# Adafruit_PCA9685_rev_C.net
KiCad netlist of a schematic drawn in EAGLE
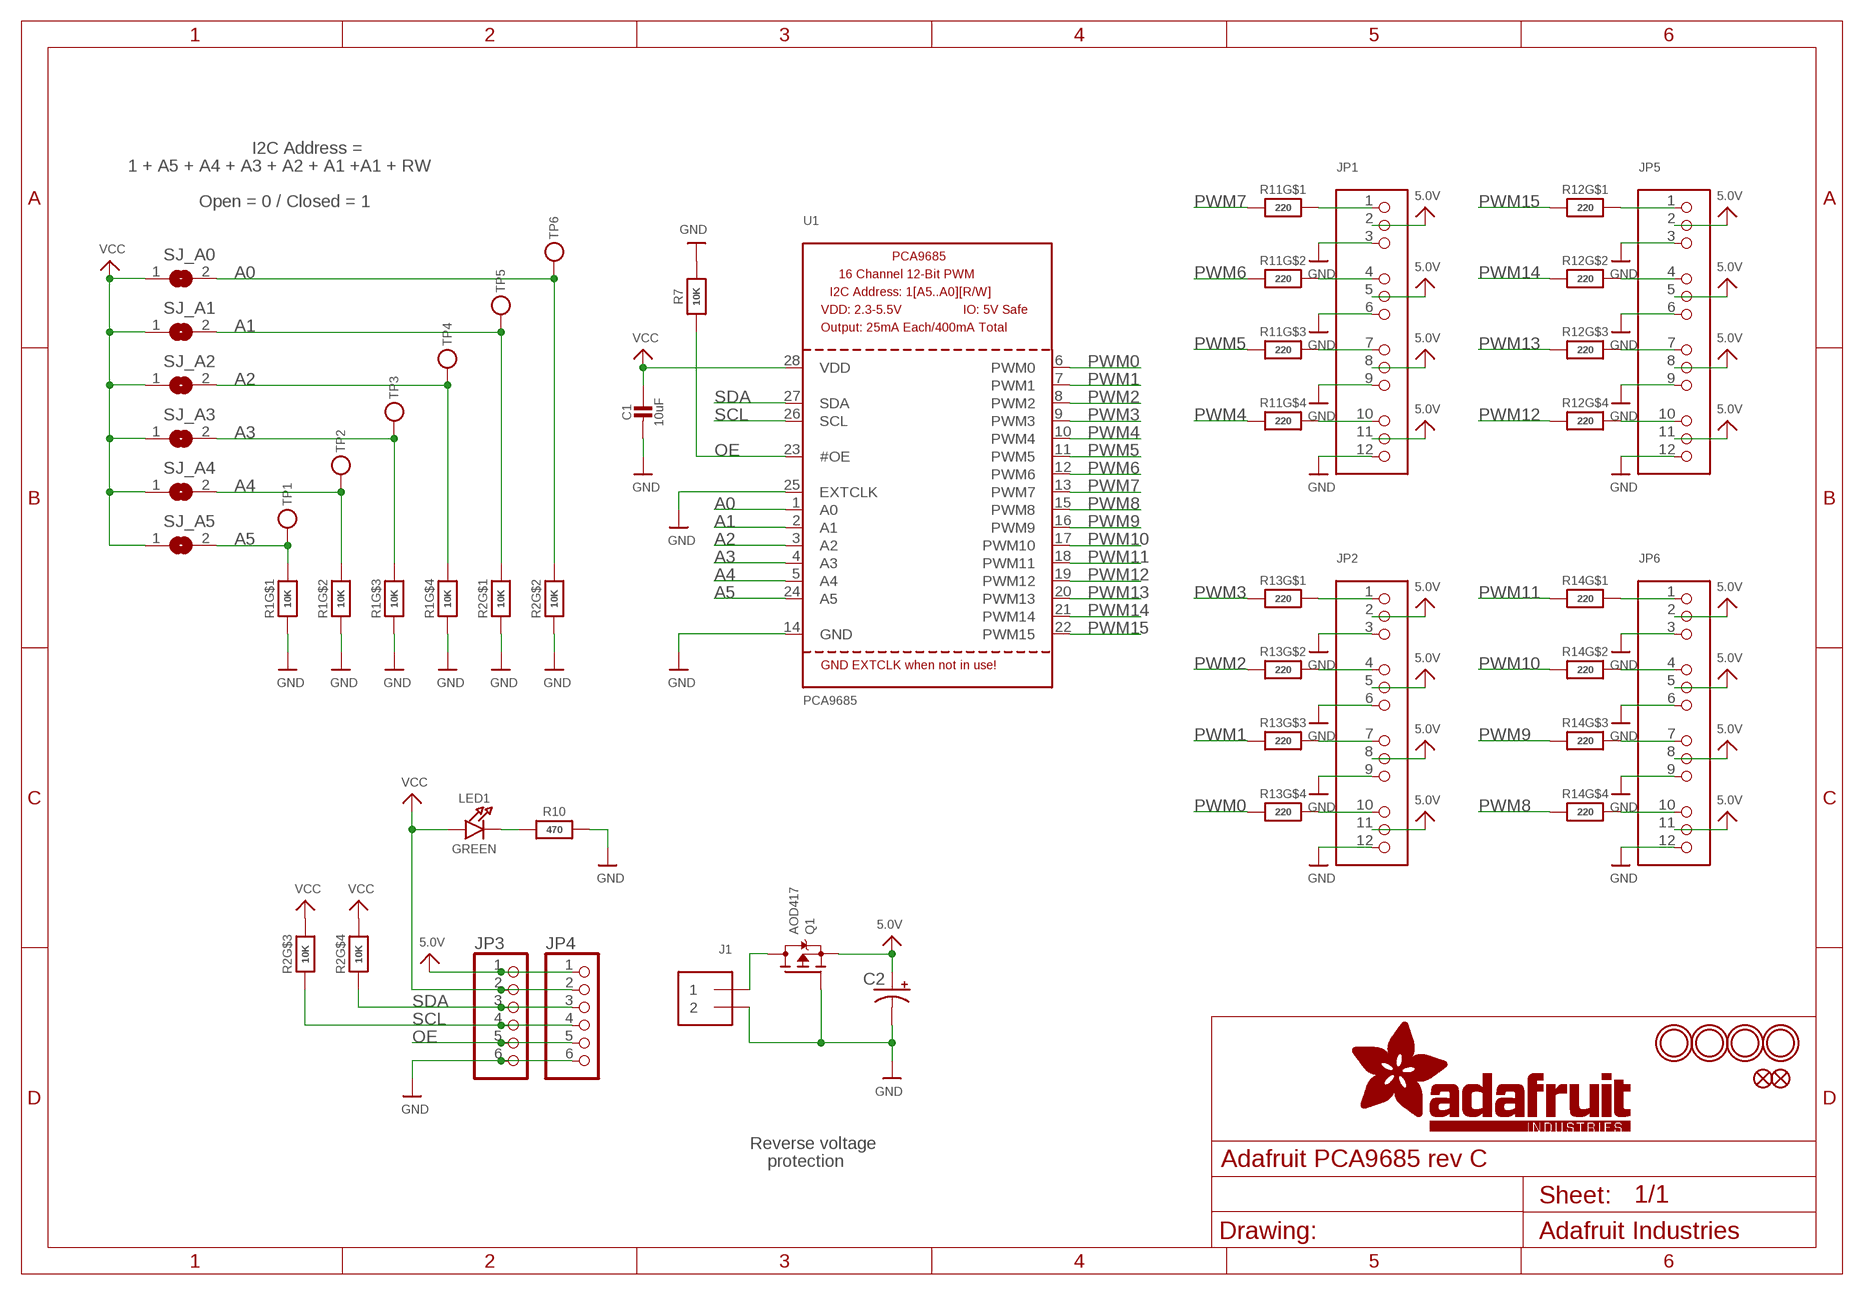
[diagram p0: schematic, sheet 1]

(export (version "E")
  (design (tool "Eeschema 10.0.6"))
  (components
    (comp (ref "C1")
      (value "10uF")
      (footprint "eagle-import:0805-NO")
      (libsource (lib "eagle-import") (part "CAP_CERAMIC0805-NOOUTLINE"))
    )
    (comp (ref "C2")
      (value "CPOL-USE3.5-8")
      (footprint "eagle-import:E3,5-8")
      (libsource (lib "eagle-import") (part "CPOL-USE3.5-8"))
    )
    (comp (ref "FID1")
      (value "FIDUCIAL\"\"")
      (footprint "eagle-import:FIDUCIAL_1MM")
      (libsource (lib "eagle-import") (part "FIDUCIAL{dblquote}{dblquote}"))
    )
    (comp (ref "FID2")
      (value "FIDUCIAL\"\"")
      (footprint "eagle-import:FIDUCIAL_1MM")
      (libsource (lib "eagle-import") (part "FIDUCIAL{dblquote}{dblquote}"))
    )
    (comp (ref "J1")
      (value "TERMBLOCK_1X2")
      (footprint "eagle-import:TERMBLOCK_1X2-3.5MM")
      (libsource (lib "eagle-import") (part "TERMBLOCK_1X2"))
    )
    (comp (ref "JP1")
      (value "HEADER-3X04")
      (footprint "eagle-import:3X04")
      (libsource (lib "eagle-import") (part "HEADER-3X04"))
    )
    (comp (ref "JP2")
      (value "HEADER-3X04")
      (footprint "eagle-import:3X04")
      (libsource (lib "eagle-import") (part "HEADER-3X04"))
    )
    (comp (ref "JP3")
      (value "PINHD-1X6CB")
      (footprint "eagle-import:1X06-CLEANBIG")
      (libsource (lib "eagle-import") (part "PINHD-1X6CB"))
    )
    (comp (ref "JP4")
      (value "PINHD-1X6CB")
      (footprint "eagle-import:1X06-CLEANBIG")
      (libsource (lib "eagle-import") (part "PINHD-1X6CB"))
    )
    (comp (ref "JP5")
      (value "HEADER-3X04")
      (footprint "eagle-import:3X04")
      (libsource (lib "eagle-import") (part "HEADER-3X04"))
    )
    (comp (ref "JP6")
      (value "HEADER-3X04")
      (footprint "eagle-import:3X04")
      (libsource (lib "eagle-import") (part "HEADER-3X04"))
    )
    (comp (ref "LED1")
      (value "GREEN")
      (footprint "eagle-import:CHIPLED_0805_NOOUTLINE")
      (libsource (lib "eagle-import") (part "LED0805_NOOUTLINE"))
    )
    (comp (ref "Q1")
      (value "AOD417")
      (footprint "eagle-import:TO252")
      (libsource (lib "eagle-import") (part "MOSFET-PTO252"))
    )
    (comp (ref "R1")
      (value "10K")
      (footprint "eagle-import:RESPACK_4X0603")
      (libsource (lib "eagle-import") (part "RESISTOR_4PACK"))
    )
    (comp (ref "R2")
      (value "10K")
      (footprint "eagle-import:RESPACK_4X0603")
      (libsource (lib "eagle-import") (part "RESISTOR_4PACK"))
    )
    (comp (ref "R7")
      (value "10K")
      (footprint "eagle-import:0805-NO")
      (libsource (lib "eagle-import") (part "RESISTOR0805_NOOUTLINE"))
    )
    (comp (ref "R10")
      (value "470")
      (footprint "eagle-import:_0805MP")
      (libsource (lib "eagle-import") (part "RESISTOR_0805MP"))
    )
    (comp (ref "R11")
      (value "220")
      (footprint "eagle-import:RESPACK_4X0603")
      (libsource (lib "eagle-import") (part "RESISTOR_4PACK"))
    )
    (comp (ref "R12")
      (value "220")
      (footprint "eagle-import:RESPACK_4X0603")
      (libsource (lib "eagle-import") (part "RESISTOR_4PACK"))
    )
    (comp (ref "R13")
      (value "220")
      (footprint "eagle-import:RESPACK_4X0603")
      (libsource (lib "eagle-import") (part "RESISTOR_4PACK"))
    )
    (comp (ref "R14")
      (value "220")
      (footprint "eagle-import:RESPACK_4X0603")
      (libsource (lib "eagle-import") (part "RESISTOR_4PACK"))
    )
    (comp (ref "SJ_A0")
      (value "SOLDERJUMPERREFLOW_NOPASTE")
      (footprint "eagle-import:SOLDERJUMPER_REFLOW_NOPASTE")
      (libsource (lib "eagle-import") (part "SOLDERJUMPERREFLOW_NOPASTE"))
    )
    (comp (ref "SJ_A1")
      (value "SOLDERJUMPERREFLOW_NOPASTE")
      (footprint "eagle-import:SOLDERJUMPER_REFLOW_NOPASTE")
      (libsource (lib "eagle-import") (part "SOLDERJUMPERREFLOW_NOPASTE"))
    )
    (comp (ref "SJ_A2")
      (value "SOLDERJUMPERREFLOW_NOPASTE")
      (footprint "eagle-import:SOLDERJUMPER_REFLOW_NOPASTE")
      (libsource (lib "eagle-import") (part "SOLDERJUMPERREFLOW_NOPASTE"))
    )
    (comp (ref "SJ_A3")
      (value "SOLDERJUMPERREFLOW_NOPASTE")
      (footprint "eagle-import:SOLDERJUMPER_REFLOW_NOPASTE")
      (libsource (lib "eagle-import") (part "SOLDERJUMPERREFLOW_NOPASTE"))
    )
    (comp (ref "SJ_A4")
      (value "SOLDERJUMPERREFLOW_NOPASTE")
      (footprint "eagle-import:SOLDERJUMPER_REFLOW_NOPASTE")
      (libsource (lib "eagle-import") (part "SOLDERJUMPERREFLOW_NOPASTE"))
    )
    (comp (ref "SJ_A5")
      (value "SOLDERJUMPERREFLOW_NOPASTE")
      (footprint "eagle-import:SOLDERJUMPER_REFLOW_NOPASTE")
      (libsource (lib "eagle-import") (part "SOLDERJUMPERREFLOW_NOPASTE"))
    )
    (comp (ref "TP1")
      (value "TESTPOINTROUND1MM")
      (footprint "eagle-import:TESTPOINT_ROUND_1MM")
      (libsource (lib "eagle-import") (part "TESTPOINTROUND1MM"))
    )
    (comp (ref "TP2")
      (value "TESTPOINTROUND1MM")
      (footprint "eagle-import:TESTPOINT_ROUND_1MM")
      (libsource (lib "eagle-import") (part "TESTPOINTROUND1MM"))
    )
    (comp (ref "TP3")
      (value "TESTPOINTROUND1MM")
      (footprint "eagle-import:TESTPOINT_ROUND_1MM")
      (libsource (lib "eagle-import") (part "TESTPOINTROUND1MM"))
    )
    (comp (ref "TP4")
      (value "TESTPOINTROUND1MM")
      (footprint "eagle-import:TESTPOINT_ROUND_1MM")
      (libsource (lib "eagle-import") (part "TESTPOINTROUND1MM"))
    )
    (comp (ref "TP5")
      (value "TESTPOINTROUND1MM")
      (footprint "eagle-import:TESTPOINT_ROUND_1MM")
      (libsource (lib "eagle-import") (part "TESTPOINTROUND1MM"))
    )
    (comp (ref "TP6")
      (value "TESTPOINTROUND1MM")
      (footprint "eagle-import:TESTPOINT_ROUND_1MM")
      (libsource (lib "eagle-import") (part "TESTPOINTROUND1MM"))
    )
    (comp (ref "U$47")
      (value "MOUNTINGHOLE2.5")
      (footprint "eagle-import:MOUNTINGHOLE_2.5_PLATED")
      (libsource (lib "eagle-import") (part "MOUNTINGHOLE2.5"))
    )
    (comp (ref "U$48")
      (value "MOUNTINGHOLE2.5")
      (footprint "eagle-import:MOUNTINGHOLE_2.5_PLATED")
      (libsource (lib "eagle-import") (part "MOUNTINGHOLE2.5"))
    )
    (comp (ref "U$49")
      (value "MOUNTINGHOLE2.5")
      (footprint "eagle-import:MOUNTINGHOLE_2.5_PLATED")
      (libsource (lib "eagle-import") (part "MOUNTINGHOLE2.5"))
    )
    (comp (ref "U$50")
      (value "MOUNTINGHOLE2.5")
      (footprint "eagle-import:MOUNTINGHOLE_2.5_PLATED")
      (libsource (lib "eagle-import") (part "MOUNTINGHOLE2.5"))
    )
    (comp (ref "U1")
      (value "PCA9685")
      (footprint "eagle-import:TSSOP28")
      (libsource (lib "eagle-import") (part "PCA9685"))
    )
  )
  (nets
    (net (code "1") (name "/A0") (class "Default")
      (node (ref "R2") (pin "7") (pinfunction "2_7") (pintype "passive"))
      (node (ref "SJ_A0") (pin "2") (pinfunction "2_2") (pintype "passive"))
      (node (ref "TP6") (pin "P$1") (pinfunction "P$1_P$1") (pintype "bidirectional"))
      (node (ref "U1") (pin "1") (pinfunction "A0_1") (pintype "bidirectional"))
    )
    (net (code "2") (name "/A1") (class "Default")
      (node (ref "R2") (pin "8") (pinfunction "2_8") (pintype "passive"))
      (node (ref "SJ_A1") (pin "2") (pinfunction "2_2") (pintype "passive"))
      (node (ref "TP5") (pin "P$1") (pinfunction "P$1_P$1") (pintype "bidirectional"))
      (node (ref "U1") (pin "2") (pinfunction "A1_2") (pintype "bidirectional"))
    )
    (net (code "3") (name "/A2") (class "Default")
      (node (ref "R1") (pin "5") (pinfunction "2_5") (pintype "passive"))
      (node (ref "SJ_A2") (pin "2") (pinfunction "2_2") (pintype "passive"))
      (node (ref "TP4") (pin "P$1") (pinfunction "P$1_P$1") (pintype "bidirectional"))
      (node (ref "U1") (pin "3") (pinfunction "A2_3") (pintype "bidirectional"))
    )
    (net (code "4") (name "/A3") (class "Default")
      (node (ref "R1") (pin "6") (pinfunction "2_6") (pintype "passive"))
      (node (ref "SJ_A3") (pin "2") (pinfunction "2_2") (pintype "passive"))
      (node (ref "TP3") (pin "P$1") (pinfunction "P$1_P$1") (pintype "bidirectional"))
      (node (ref "U1") (pin "4") (pinfunction "A3_4") (pintype "bidirectional"))
    )
    (net (code "5") (name "/A4") (class "Default")
      (node (ref "R1") (pin "7") (pinfunction "2_7") (pintype "passive"))
      (node (ref "SJ_A4") (pin "2") (pinfunction "2_2") (pintype "passive"))
      (node (ref "TP2") (pin "P$1") (pinfunction "P$1_P$1") (pintype "bidirectional"))
      (node (ref "U1") (pin "5") (pinfunction "A4_5") (pintype "bidirectional"))
    )
    (net (code "6") (name "/A5") (class "Default")
      (node (ref "R1") (pin "8") (pinfunction "2_8") (pintype "passive"))
      (node (ref "SJ_A5") (pin "2") (pinfunction "2_2") (pintype "passive"))
      (node (ref "TP1") (pin "P$1") (pinfunction "P$1_P$1") (pintype "bidirectional"))
      (node (ref "U1") (pin "24") (pinfunction "A5_24") (pintype "bidirectional"))
    )
    (net (code "7") (name "/OE") (class "Default")
      (node (ref "JP3") (pin "5") (pinfunction "5_5") (pintype "passive"))
      (node (ref "JP4") (pin "5") (pinfunction "5_5") (pintype "passive"))
      (node (ref "R7") (pin "1") (pinfunction "1_1") (pintype "passive"))
      (node (ref "U1") (pin "23") (pinfunction "#OE_23") (pintype "input"))
    )
    (net (code "8") (name "/PWM0") (class "Default")
      (node (ref "R13") (pin "4") (pinfunction "1_4") (pintype "passive"))
      (node (ref "U1") (pin "6") (pinfunction "PWM0_6") (pintype "output"))
    )
    (net (code "9") (name "/PWM1") (class "Default")
      (node (ref "R13") (pin "3") (pinfunction "1_3") (pintype "passive"))
      (node (ref "U1") (pin "7") (pinfunction "PWM1_7") (pintype "output"))
    )
    (net (code "10") (name "/PWM2") (class "Default")
      (node (ref "R13") (pin "2") (pinfunction "1_2") (pintype "passive"))
      (node (ref "U1") (pin "8") (pinfunction "PWM2_8") (pintype "output"))
    )
    (net (code "11") (name "/PWM3") (class "Default")
      (node (ref "R13") (pin "1") (pinfunction "1_1") (pintype "passive"))
      (node (ref "U1") (pin "9") (pinfunction "PWM3_9") (pintype "output"))
    )
    (net (code "12") (name "/PWM4") (class "Default")
      (node (ref "R11") (pin "4") (pinfunction "1_4") (pintype "passive"))
      (node (ref "U1") (pin "10") (pinfunction "PWM4_10") (pintype "output"))
    )
    (net (code "13") (name "/PWM5") (class "Default")
      (node (ref "R11") (pin "3") (pinfunction "1_3") (pintype "passive"))
      (node (ref "U1") (pin "11") (pinfunction "PWM5_11") (pintype "output"))
    )
    (net (code "14") (name "/PWM6") (class "Default")
      (node (ref "R11") (pin "2") (pinfunction "1_2") (pintype "passive"))
      (node (ref "U1") (pin "12") (pinfunction "PWM6_12") (pintype "output"))
    )
    (net (code "15") (name "/PWM7") (class "Default")
      (node (ref "R11") (pin "1") (pinfunction "1_1") (pintype "passive"))
      (node (ref "U1") (pin "13") (pinfunction "PWM7_13") (pintype "output"))
    )
    (net (code "16") (name "/PWM8") (class "Default")
      (node (ref "R14") (pin "4") (pinfunction "1_4") (pintype "passive"))
      (node (ref "U1") (pin "15") (pinfunction "PWM8_15") (pintype "output"))
    )
    (net (code "17") (name "/PWM9") (class "Default")
      (node (ref "R14") (pin "3") (pinfunction "1_3") (pintype "passive"))
      (node (ref "U1") (pin "16") (pinfunction "PWM9_16") (pintype "output"))
    )
    (net (code "18") (name "/PWM10") (class "Default")
      (node (ref "R14") (pin "2") (pinfunction "1_2") (pintype "passive"))
      (node (ref "U1") (pin "17") (pinfunction "PWM10_17") (pintype "output"))
    )
    (net (code "19") (name "/PWM11") (class "Default")
      (node (ref "R14") (pin "1") (pinfunction "1_1") (pintype "passive"))
      (node (ref "U1") (pin "18") (pinfunction "PWM11_18") (pintype "output"))
    )
    (net (code "20") (name "/PWM12") (class "Default")
      (node (ref "R12") (pin "4") (pinfunction "1_4") (pintype "passive"))
      (node (ref "U1") (pin "19") (pinfunction "PWM12_19") (pintype "output"))
    )
    (net (code "21") (name "/PWM13") (class "Default")
      (node (ref "R12") (pin "3") (pinfunction "1_3") (pintype "passive"))
      (node (ref "U1") (pin "20") (pinfunction "PWM13_20") (pintype "output"))
    )
    (net (code "22") (name "/PWM14") (class "Default")
      (node (ref "R12") (pin "2") (pinfunction "1_2") (pintype "passive"))
      (node (ref "U1") (pin "21") (pinfunction "PWM14_21") (pintype "output"))
    )
    (net (code "23") (name "/PWM15") (class "Default")
      (node (ref "R12") (pin "1") (pinfunction "1_1") (pintype "passive"))
      (node (ref "U1") (pin "22") (pinfunction "PWM15_22") (pintype "output"))
    )
    (net (code "24") (name "/SCL") (class "Default")
      (node (ref "JP3") (pin "4") (pinfunction "4_4") (pintype "passive"))
      (node (ref "JP4") (pin "4") (pinfunction "4_4") (pintype "passive"))
      (node (ref "R2") (pin "3") (pinfunction "1_3") (pintype "passive"))
      (node (ref "U1") (pin "26") (pinfunction "SCL_26") (pintype "bidirectional"))
    )
    (net (code "25") (name "/SDA") (class "Default")
      (node (ref "JP3") (pin "3") (pinfunction "3_3") (pintype "passive"))
      (node (ref "JP4") (pin "3") (pinfunction "3_3") (pintype "passive"))
      (node (ref "R2") (pin "4") (pinfunction "1_4") (pintype "passive"))
      (node (ref "U1") (pin "27") (pinfunction "SDA_27") (pintype "bidirectional"))
    )
    (net (code "26") (name "5.0V") (class "Default")
      (node (ref "C2") (pin "+") (pinfunction "+_+") (pintype "passive"))
      (node (ref "JP1") (pin "11") (pinfunction "11_11") (pintype "passive"))
      (node (ref "JP1") (pin "2") (pinfunction "2_2") (pintype "passive"))
      (node (ref "JP1") (pin "5") (pinfunction "5_5") (pintype "passive"))
      (node (ref "JP1") (pin "8") (pinfunction "8_8") (pintype "passive"))
      (node (ref "JP2") (pin "11") (pinfunction "11_11") (pintype "passive"))
      (node (ref "JP2") (pin "2") (pinfunction "2_2") (pintype "passive"))
      (node (ref "JP2") (pin "5") (pinfunction "5_5") (pintype "passive"))
      (node (ref "JP2") (pin "8") (pinfunction "8_8") (pintype "passive"))
      (node (ref "JP3") (pin "1") (pinfunction "1_1") (pintype "passive"))
      (node (ref "JP4") (pin "1") (pinfunction "1_1") (pintype "passive"))
      (node (ref "JP5") (pin "11") (pinfunction "11_11") (pintype "passive"))
      (node (ref "JP5") (pin "2") (pinfunction "2_2") (pintype "passive"))
      (node (ref "JP5") (pin "5") (pinfunction "5_5") (pintype "passive"))
      (node (ref "JP5") (pin "8") (pinfunction "8_8") (pintype "passive"))
      (node (ref "JP6") (pin "11") (pinfunction "11_11") (pintype "passive"))
      (node (ref "JP6") (pin "2") (pinfunction "2_2") (pintype "passive"))
      (node (ref "JP6") (pin "5") (pinfunction "5_5") (pintype "passive"))
      (node (ref "JP6") (pin "8") (pinfunction "8_8") (pintype "passive"))
      (node (ref "Q1") (pin "2") (pinfunction "S_2") (pintype "passive"))
    )
    (net (code "27") (name "GND") (class "Default")
      (node (ref "C1") (pin "2") (pinfunction "2_2") (pintype "passive"))
      (node (ref "C2") (pin "-") (pinfunction "-_-") (pintype "passive"))
      (node (ref "J1") (pin "2") (pinfunction "2_2") (pintype "passive"))
      (node (ref "JP1") (pin "12") (pinfunction "12_12") (pintype "passive"))
      (node (ref "JP1") (pin "3") (pinfunction "3_3") (pintype "passive"))
      (node (ref "JP1") (pin "6") (pinfunction "6_6") (pintype "passive"))
      (node (ref "JP1") (pin "9") (pinfunction "9_9") (pintype "passive"))
      (node (ref "JP2") (pin "12") (pinfunction "12_12") (pintype "passive"))
      (node (ref "JP2") (pin "3") (pinfunction "3_3") (pintype "passive"))
      (node (ref "JP2") (pin "6") (pinfunction "6_6") (pintype "passive"))
      (node (ref "JP2") (pin "9") (pinfunction "9_9") (pintype "passive"))
      (node (ref "JP3") (pin "6") (pinfunction "6_6") (pintype "passive"))
      (node (ref "JP4") (pin "6") (pinfunction "6_6") (pintype "passive"))
      (node (ref "JP5") (pin "12") (pinfunction "12_12") (pintype "passive"))
      (node (ref "JP5") (pin "3") (pinfunction "3_3") (pintype "passive"))
      (node (ref "JP5") (pin "6") (pinfunction "6_6") (pintype "passive"))
      (node (ref "JP5") (pin "9") (pinfunction "9_9") (pintype "passive"))
      (node (ref "JP6") (pin "12") (pinfunction "12_12") (pintype "passive"))
      (node (ref "JP6") (pin "3") (pinfunction "3_3") (pintype "passive"))
      (node (ref "JP6") (pin "6") (pinfunction "6_6") (pintype "passive"))
      (node (ref "JP6") (pin "9") (pinfunction "9_9") (pintype "passive"))
      (node (ref "Q1") (pin "1") (pinfunction "G_1") (pintype "passive"))
      (node (ref "R1") (pin "1") (pinfunction "1_1") (pintype "passive"))
      (node (ref "R1") (pin "2") (pinfunction "1_2") (pintype "passive"))
      (node (ref "R1") (pin "3") (pinfunction "1_3") (pintype "passive"))
      (node (ref "R1") (pin "4") (pinfunction "1_4") (pintype "passive"))
      (node (ref "R10") (pin "2") (pinfunction "2_2") (pintype "passive"))
      (node (ref "R2") (pin "1") (pinfunction "1_1") (pintype "passive"))
      (node (ref "R2") (pin "2") (pinfunction "1_2") (pintype "passive"))
      (node (ref "R7") (pin "2") (pinfunction "2_2") (pintype "passive"))
      (node (ref "U1") (pin "14") (pinfunction "GND_14") (pintype "power_in"))
      (node (ref "U1") (pin "25") (pinfunction "EXTCLK_25") (pintype "input"))
    )
    (net (code "28") (name "Net-(LED1-PadC)") (class "Default")
      (node (ref "LED1") (pin "C") (pinfunction "C_C") (pintype "passive"))
      (node (ref "R10") (pin "1") (pinfunction "1_1") (pintype "passive"))
    )
    (net (code "29") (name "Net-(Q1-D)") (class "Default")
      (node (ref "J1") (pin "1") (pinfunction "1_1") (pintype "passive"))
      (node (ref "Q1") (pin "3") (pinfunction "D_3") (pintype "passive"))
    )
    (net (code "30") (name "Net-(R11A-2)") (class "Default")
      (node (ref "JP1") (pin "1") (pinfunction "1_1") (pintype "passive"))
      (node (ref "R11") (pin "8") (pinfunction "2_8") (pintype "passive"))
    )
    (net (code "31") (name "Net-(R11B-2)") (class "Default")
      (node (ref "JP1") (pin "4") (pinfunction "4_4") (pintype "passive"))
      (node (ref "R11") (pin "7") (pinfunction "2_7") (pintype "passive"))
    )
    (net (code "32") (name "Net-(R11C-2)") (class "Default")
      (node (ref "JP1") (pin "7") (pinfunction "7_7") (pintype "passive"))
      (node (ref "R11") (pin "6") (pinfunction "2_6") (pintype "passive"))
    )
    (net (code "33") (name "Net-(R11D-2)") (class "Default")
      (node (ref "JP1") (pin "10") (pinfunction "10_10") (pintype "passive"))
      (node (ref "R11") (pin "5") (pinfunction "2_5") (pintype "passive"))
    )
    (net (code "34") (name "Net-(R12A-2)") (class "Default")
      (node (ref "JP5") (pin "1") (pinfunction "1_1") (pintype "passive"))
      (node (ref "R12") (pin "8") (pinfunction "2_8") (pintype "passive"))
    )
    (net (code "35") (name "Net-(R12B-2)") (class "Default")
      (node (ref "JP5") (pin "4") (pinfunction "4_4") (pintype "passive"))
      (node (ref "R12") (pin "7") (pinfunction "2_7") (pintype "passive"))
    )
    (net (code "36") (name "Net-(R12C-2)") (class "Default")
      (node (ref "JP5") (pin "7") (pinfunction "7_7") (pintype "passive"))
      (node (ref "R12") (pin "6") (pinfunction "2_6") (pintype "passive"))
    )
    (net (code "37") (name "Net-(R12D-2)") (class "Default")
      (node (ref "JP5") (pin "10") (pinfunction "10_10") (pintype "passive"))
      (node (ref "R12") (pin "5") (pinfunction "2_5") (pintype "passive"))
    )
    (net (code "38") (name "Net-(R13A-2)") (class "Default")
      (node (ref "JP2") (pin "1") (pinfunction "1_1") (pintype "passive"))
      (node (ref "R13") (pin "8") (pinfunction "2_8") (pintype "passive"))
    )
    (net (code "39") (name "Net-(R13B-2)") (class "Default")
      (node (ref "JP2") (pin "4") (pinfunction "4_4") (pintype "passive"))
      (node (ref "R13") (pin "7") (pinfunction "2_7") (pintype "passive"))
    )
    (net (code "40") (name "Net-(R13C-2)") (class "Default")
      (node (ref "JP2") (pin "7") (pinfunction "7_7") (pintype "passive"))
      (node (ref "R13") (pin "6") (pinfunction "2_6") (pintype "passive"))
    )
    (net (code "41") (name "Net-(R13D-2)") (class "Default")
      (node (ref "JP2") (pin "10") (pinfunction "10_10") (pintype "passive"))
      (node (ref "R13") (pin "5") (pinfunction "2_5") (pintype "passive"))
    )
    (net (code "42") (name "Net-(R14A-2)") (class "Default")
      (node (ref "JP6") (pin "1") (pinfunction "1_1") (pintype "passive"))
      (node (ref "R14") (pin "8") (pinfunction "2_8") (pintype "passive"))
    )
    (net (code "43") (name "Net-(R14B-2)") (class "Default")
      (node (ref "JP6") (pin "4") (pinfunction "4_4") (pintype "passive"))
      (node (ref "R14") (pin "7") (pinfunction "2_7") (pintype "passive"))
    )
    (net (code "44") (name "Net-(R14C-2)") (class "Default")
      (node (ref "JP6") (pin "7") (pinfunction "7_7") (pintype "passive"))
      (node (ref "R14") (pin "6") (pinfunction "2_6") (pintype "passive"))
    )
    (net (code "45") (name "Net-(R14D-2)") (class "Default")
      (node (ref "JP6") (pin "10") (pinfunction "10_10") (pintype "passive"))
      (node (ref "R14") (pin "5") (pinfunction "2_5") (pintype "passive"))
    )
    (net (code "46") (name "VCC") (class "Default")
      (node (ref "C1") (pin "1") (pinfunction "1_1") (pintype "passive"))
      (node (ref "JP3") (pin "2") (pinfunction "2_2") (pintype "passive"))
      (node (ref "JP4") (pin "2") (pinfunction "2_2") (pintype "passive"))
      (node (ref "LED1") (pin "A") (pinfunction "A_A") (pintype "passive"))
      (node (ref "R2") (pin "5") (pinfunction "2_5") (pintype "passive"))
      (node (ref "R2") (pin "6") (pinfunction "2_6") (pintype "passive"))
      (node (ref "SJ_A0") (pin "1") (pinfunction "1_1") (pintype "passive"))
      (node (ref "SJ_A1") (pin "1") (pinfunction "1_1") (pintype "passive"))
      (node (ref "SJ_A2") (pin "1") (pinfunction "1_1") (pintype "passive"))
      (node (ref "SJ_A3") (pin "1") (pinfunction "1_1") (pintype "passive"))
      (node (ref "SJ_A4") (pin "1") (pinfunction "1_1") (pintype "passive"))
      (node (ref "SJ_A5") (pin "1") (pinfunction "1_1") (pintype "passive"))
      (node (ref "U1") (pin "28") (pinfunction "VDD_28") (pintype "power_in"))
    )
  )
)
